# Charger_CAN_Interface_-_Charger_Relay.net
KiCad netlist of a schematic drawn in Altium Designer
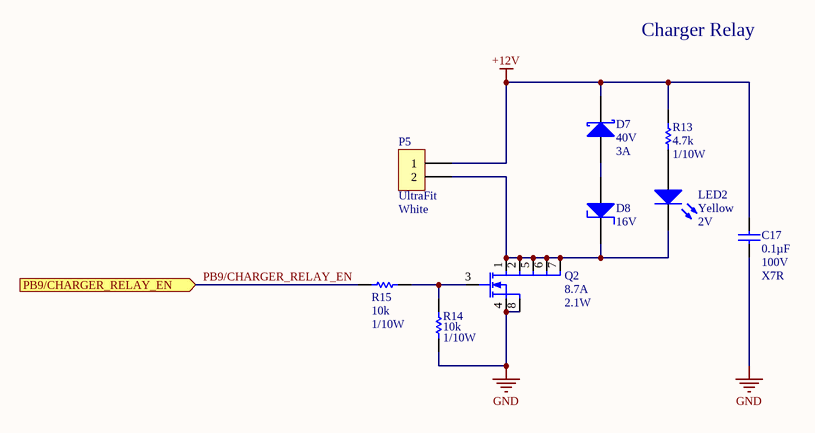
[diagram p0: Charger CAN Interface - Charger Relay.SchDoc]

(export (version "E")
  (design (tool "Eeschema 10.0.6"))
  (components
    (comp (ref "C17")
      (value "CAP CER 0.1UF 100V 10% X7R 0805")
      (footprint "CAP, 0805")
      (description "0.1µF ±10% 100V Ceramic Capacitor X7R 0805 (2012 Metric)")
      (fields
        (field (name "TOLERANCE") "±10%")
        (field (name "CAPACITANCE") "0.1µF")
        (field (name "VOLTAGE") "100V")
        (field (name "TEMPERATURE COEFFICIENT") "X7R")
      )
      (libsource (lib "Schematic Diagrams") (part "CAP CER 0.1UF 100V 10% X7R 0805"))
    )
    (comp (ref "D7")
      (value "DIODE SCHOTTKY 40V 3A DO-214AA (SMB)")
      (footprint "DO-214AA Diode")
      (description "Diode Schottky 40V 3A Surface Mount DO-214AA (SMB)")
      (fields
        (field (name "VOLTAGE - DC REVERSE (VR) (MAX)") "40V")
        (field (name "CURRENT - AVERAGE RECTIFIED (IO)") "3A")
      )
      (libsource (lib "Schematic Diagrams") (part "DIODE SCHOTTKY 40V 3A DO-214AA (SMB)"))
    )
    (comp (ref "D8")
      (value "DIODE ZENER 16V 5W DO-214AA (SMB)")
      (footprint "DO-214AA Diode")
      (description "Zener Diode 16V 5W ±5% Surface Mount DO-214AA (SMB)")
      (fields
        (field (name "MANUFACTURE PART NUMBER") "SMBJ5353B-TP")
        (field (name "VOLTAGE - ZENER (NOM)") "16V")
      )
      (libsource (lib "Schematic Diagrams") (part "DIODE ZENER 16V 5W DO-214AA (SMB)"))
    )
    (comp (ref "LED2")
      (value "LED YELLOW CLEAR 2.1V 0603")
      (footprint "LED_0603")
      (description "Yellow 590nm LED Indication - Discrete 2V 0603 (1608 Metric)")
      (fields
        (field (name "MANUFACTURER") "Wurth Electronics Inc.")
        (field (name "MANUFACTURER PART NUMBER") "150060YS75000")
        (field (name "COLOR") "Yellow")
        (field (name "VOLTAGE - FORWARD (VF) (TYP)") "2V")
      )
      (libsource (lib "Schematic Diagrams") (part "LED YELLOW CLEAR 2.1V 0603"))
    )
    (comp (ref "P5")
      (value "CONN 2POS ULTRA-FIT NATURAL COLOR 0.138\"")
      (footprint "CONN, 2POS ULTRA-FIT - NATURAL COLOR")
      (description "2 Positions Header, Shrouded Connector 0.138\" (3.50mm) Through Hole")
      (fields
        (field (name "VOLTAGE") "400V")
        (field (name "SERIES") "UltraFit")
        (field (name "COLOR") "White")
      )
      (libsource (lib "Schematic Diagrams") (part "CONN 2POS ULTRA-FIT NATURAL COLOR 0.138{dblquote}"))
    )
    (comp (ref "Q2")
      (value "MOSFET N-CH 30V 8.7A 2.1W 6-PQFN (2x2)")
      (footprint "MOSFET N-CH 30V 12A 2mmx2mm PQFN")
      (fields
        (field (name "CURRENT - CONTINUOUS DRAIN (ID) @ 25°C") "8.7A")
        (field (name "POWER DISSIPATION (MAX)") "2.1W")
      )
      (libsource (lib "Schematic Diagrams") (part "MOSFET N-CH 30V 8.7A 2.1W 6-PQFN (2x2)"))
    )
    (comp (ref "R13")
      (value "RES 4.7K OHM 1% 1/10W 0603")
      (footprint "RES, 0603")
      (description "4.7k Ohm ±1% 0.1W, 1/10W Chip Resistor 0603 (1608 Metric) Moisture Resistant Thick Film")
      (fields
        (field (name "TOLERANCE") "±1%")
        (field (name "RESISTANCE (OHMS)") "4.7k")
        (field (name "POWER (WATTS)") "1/10W")
      )
      (libsource (lib "Schematic Diagrams") (part "RES 4.7K OHM 1% 1/10W 0603"))
    )
    (comp (ref "R14")
      (value "RES 10K OHM 1% 1/10W 0603")
      (footprint "RES, 0603")
      (description "RES SMD 10K OHM 1% 1/10W 0603")
      (fields
        (field (name "TOLERANCE") "±1%")
        (field (name "RESISTANCE") "10k")
        (field (name "POWER") "1/10W")
      )
      (libsource (lib "Schematic Diagrams") (part "RES 10K OHM 1% 1/10W 0603"))
    )
    (comp (ref "R15")
      (value "RES 10K OHM 1% 1/10W 0603")
      (footprint "RES, 0603")
      (description "RES SMD 10K OHM 1% 1/10W 0603")
      (fields
        (field (name "TOLERANCE") "±1%")
        (field (name "RESISTANCE") "10k")
        (field (name "POWER") "1/10W")
      )
      (libsource (lib "Schematic Diagrams") (part "RES 10K OHM 1% 1/10W 0603"))
    )
  )
  (nets
    (net (code "1") (name "+12V") (class "Default")
      (node (ref "C17") (pin "1") (pinfunction "1_1") (pintype "passive"))
      (node (ref "D7") (pin "2") (pinfunction "K_2") (pintype "passive"))
      (node (ref "P5") (pin "1") (pinfunction "1_1") (pintype "passive"))
      (node (ref "R13") (pin "1") (pinfunction "1_1") (pintype "passive"))
    )
    (net (code "2") (name "/PB9{slash}CHARGER_RELAY_EN") (class "Default")
      (node (ref "R15") (pin "1") (pinfunction "1_1") (pintype "passive"))
    )
    (net (code "3") (name "GND") (class "Default")
      (node (ref "C17") (pin "2") (pinfunction "2_2") (pintype "passive"))
      (node (ref "Q2") (pin "4") (pinfunction "S_4") (pintype "passive"))
      (node (ref "Q2") (pin "8") (pinfunction "S_8") (pintype "passive"))
      (node (ref "R14") (pin "2") (pinfunction "2_2") (pintype "passive"))
    )
    (net (code "4") (name "Net-(D7-A)") (class "Default")
      (node (ref "D7") (pin "1") (pinfunction "A_1") (pintype "passive"))
      (node (ref "D8") (pin "1") (pinfunction "A_1") (pintype "passive"))
    )
    (net (code "5") (name "Net-(D8-K)") (class "Default")
      (node (ref "D8") (pin "2") (pinfunction "K_2") (pintype "passive"))
      (node (ref "LED2") (pin "2") (pinfunction "K_2") (pintype "passive"))
      (node (ref "P5") (pin "2") (pinfunction "2_2") (pintype "passive"))
      (node (ref "Q2") (pin "1") (pinfunction "D_1") (pintype "passive"))
      (node (ref "Q2") (pin "2") (pinfunction "D_2") (pintype "passive"))
      (node (ref "Q2") (pin "5") (pinfunction "D_5") (pintype "passive"))
      (node (ref "Q2") (pin "6") (pinfunction "D_6") (pintype "passive"))
      (node (ref "Q2") (pin "7") (pinfunction "D_7") (pintype "passive"))
    )
    (net (code "6") (name "Net-(LED2-A)") (class "Default")
      (node (ref "LED2") (pin "1") (pinfunction "A_1") (pintype "passive"))
      (node (ref "R13") (pin "2") (pinfunction "2_2") (pintype "passive"))
    )
    (net (code "7") (name "Net-(Q2-G)") (class "Default")
      (node (ref "Q2") (pin "3") (pinfunction "G_3") (pintype "passive"))
      (node (ref "R14") (pin "1") (pinfunction "1_1") (pintype "passive"))
      (node (ref "R15") (pin "2") (pinfunction "2_2") (pintype "passive"))
    )
  )
)
